# Altium.net
KiCad netlist of a schematic drawn in Altium Designer
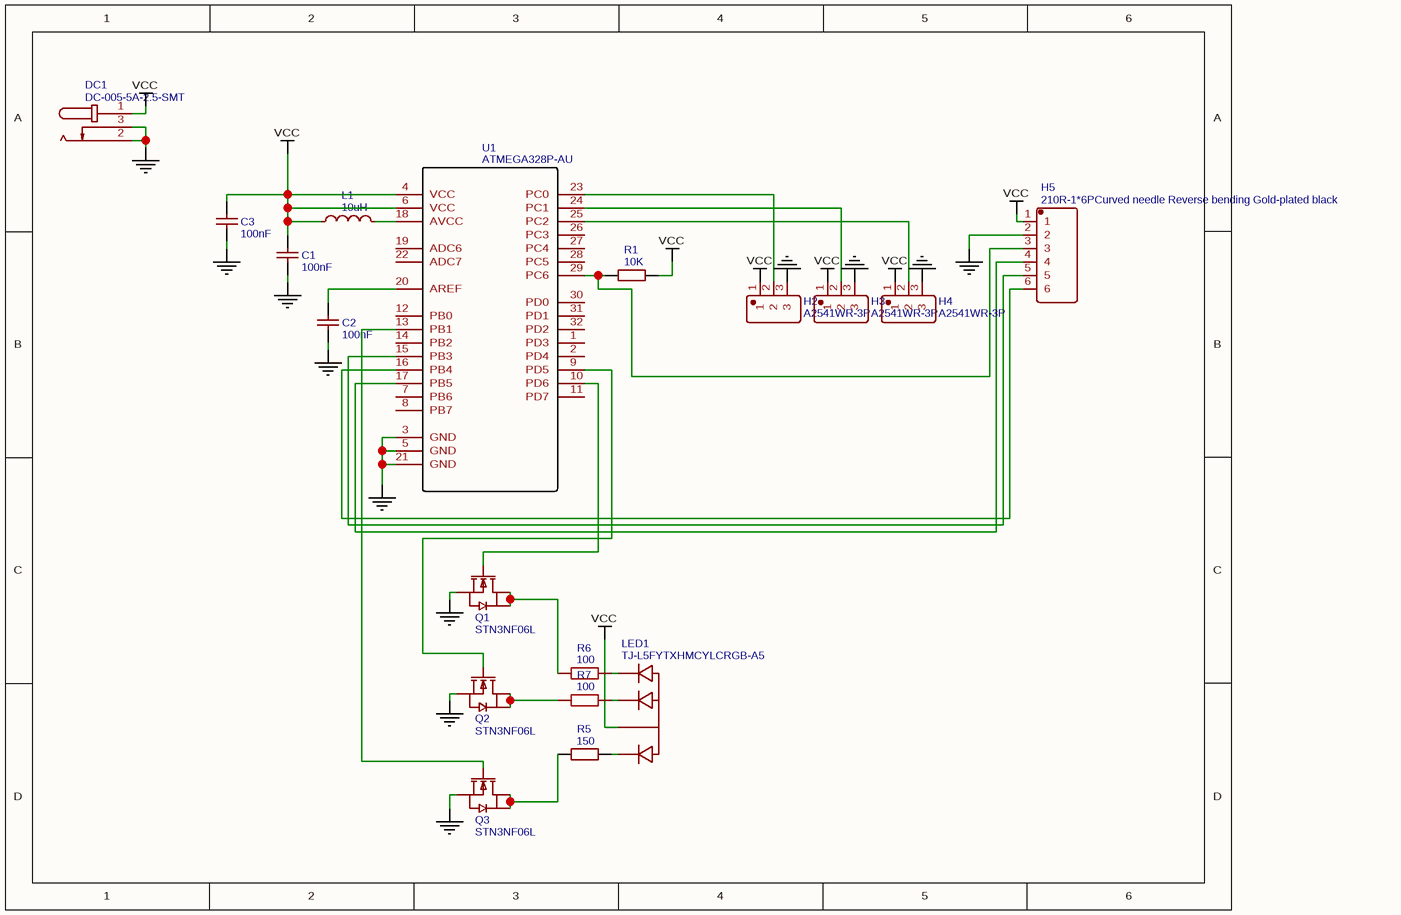
[diagram p0: Altium.schdoc]

(export (version "E")
  (design (tool "Eeschema 10.0.6"))
  (components
    (comp (ref "C1")
      (value "100nF")
      (fields
        (field (name "BOM_MANUFACTURER PART") "CC1206KKX7R0BB104")
        (field (name "BOM_SUPPLIER PART") "C107181")
      )
      (libsource (lib "altium-import") (part "root_1_100nF_"))
    )
    (comp (ref "C2")
      (value "100nF")
      (fields
        (field (name "BOM_MANUFACTURER PART") "CC1206KKX7R0BB104")
        (field (name "BOM_SUPPLIER PART") "C107181")
      )
      (libsource (lib "altium-import") (part "root_1_100nF_"))
    )
    (comp (ref "C3")
      (value "100nF")
      (fields
        (field (name "BOM_MANUFACTURER PART") "CC1206KKX7R0BB104")
        (field (name "BOM_SUPPLIER PART") "C107181")
      )
      (libsource (lib "altium-import") (part "root_1_100nF_"))
    )
    (comp (ref "DC1")
      (value "DC-005-5A-2.5-SMT")
      (fields (field (name "BOM_SUPPLIER PART") "C319133") (field (name "CONTRIBUTOR") "LCSC"))
      (libsource (lib "altium-import") (part "root_0_DC-005-5A-2.5-SMT_"))
    )
    (comp (ref "H2")
      (value "A2541WR-3P")
      (fields (field (name "BOM_SUPPLIER PART") "C225489") (field (name "CONTRIBUTOR") "LCSC"))
      (libsource (lib "altium-import") (part "root_2_A2541WR-3P_"))
    )
    (comp (ref "H3")
      (value "A2541WR-3P")
      (fields (field (name "BOM_SUPPLIER PART") "C225489") (field (name "CONTRIBUTOR") "LCSC"))
      (libsource (lib "altium-import") (part "root_2_A2541WR-3P_"))
    )
    (comp (ref "H4")
      (value "A2541WR-3P")
      (fields (field (name "BOM_SUPPLIER PART") "C225489") (field (name "CONTRIBUTOR") "LCSC"))
      (libsource (lib "altium-import") (part "root_2_A2541WR-3P_"))
    )
    (comp (ref "H5")
      (value "210R-1*6PCurved needle Reverse bending Gold-plated black")
      (fields (field (name "BOM_SUPPLIER PART") "C124367") (field (name "CONTRIBUTOR") "LCSC"))
      (libsource (lib "altium-import") (part "root_0_210R-1*6PCurved needle Reverse bending Gold-plated black_"))
    )
    (comp (ref "L1")
      (value "10uH")
      (fields
        (field (name "BOM_MANUFACTURER PART") "CMP321609XD100KT")
        (field (name "BOM_SUPPLIER PART") "C139251")
      )
      (libsource (lib "altium-import") (part "root_0_10uH_"))
    )
    (comp (ref "LED1")
      (value "TJ-L5FYTXHMCYLCRGB-A5")
      (fields (field (name "BOM_SUPPLIER PART") "C331057") (field (name "CONTRIBUTOR") "LCSC"))
      (libsource (lib "altium-import") (part "root_3_TJ-L5FYTXHMCYLCRGB-A5_"))
    )
    (comp (ref "Q1")
      (value "STN3NF06L")
      (fields (field (name "BOM_SUPPLIER PART") "C222218") (field (name "CONTRIBUTOR") "LCSC"))
      (libsource (lib "altium-import") (part "root_3_STN3NF06L_"))
    )
    (comp (ref "Q2")
      (value "STN3NF06L")
      (fields (field (name "BOM_SUPPLIER PART") "C222218") (field (name "CONTRIBUTOR") "LCSC"))
      (libsource (lib "altium-import") (part "root_3_STN3NF06L_"))
    )
    (comp (ref "Q3")
      (value "STN3NF06L")
      (fields (field (name "BOM_SUPPLIER PART") "C222218") (field (name "CONTRIBUTOR") "LCSC"))
      (libsource (lib "altium-import") (part "root_3_STN3NF06L_"))
    )
    (comp (ref "R1")
      (value "10K")
      (fields
        (field (name "BOM_MANUFACTURER PART") "1206W4F1002T5E")
        (field (name "BOM_SUPPLIER PART") "C17902")
      )
      (libsource (lib "altium-import") (part "root_0_10K_"))
    )
    (comp (ref "R5")
      (value "150")
      (fields
        (field (name "BOM_MANUFACTURER PART") "1206W4F1500T5E")
        (field (name "BOM_SUPPLIER PART") "C17917")
      )
      (libsource (lib "altium-import") (part "root_0_150_"))
    )
    (comp (ref "R6")
      (value "100")
      (fields
        (field (name "BOM_SUPPLIER PART") "C319959")
        (field (name "BOM_MANUFACTURER PART") "AR06DTCV1000")
        (field (name "CONTRIBUTOR") "LCSC")
      )
      (libsource (lib "altium-import") (part "root_0_100_"))
    )
    (comp (ref "R7")
      (value "100")
      (fields
        (field (name "BOM_SUPPLIER PART") "C319959")
        (field (name "BOM_MANUFACTURER PART") "AR06DTCV1000")
        (field (name "CONTRIBUTOR") "LCSC")
      )
      (libsource (lib "altium-import") (part "root_0_100_"))
    )
    (comp (ref "U1")
      (value "ATMEGA328P-AU")
      (fields (field (name "BOM_SUPPLIER PART") "C14877"))
      (libsource (lib "altium-import") (part "root_0_ATMEGA328P-AU_"))
    )
  )
  (nets
    (net (code "1") (name "GND") (class "Default")
      (node (ref "C1") (pin "1") (pinfunction "1_1") (pintype "passive"))
      (node (ref "C2") (pin "1") (pinfunction "1_1") (pintype "passive"))
      (node (ref "C3") (pin "1") (pinfunction "1_1") (pintype "passive"))
      (node (ref "DC1") (pin "2") (pinfunction "2_2") (pintype "passive"))
      (node (ref "DC1") (pin "3") (pinfunction "3_3") (pintype "passive"))
      (node (ref "H2") (pin "3") (pinfunction "3_3") (pintype "passive"))
      (node (ref "H3") (pin "3") (pinfunction "3_3") (pintype "passive"))
      (node (ref "H4") (pin "3") (pinfunction "3_3") (pintype "passive"))
      (node (ref "H5") (pin "2") (pinfunction "2_2") (pintype "passive"))
      (node (ref "Q1") (pin "3") (pinfunction "S_3") (pintype "passive"))
      (node (ref "Q2") (pin "3") (pinfunction "S_3") (pintype "passive"))
      (node (ref "Q3") (pin "3") (pinfunction "S_3") (pintype "passive"))
      (node (ref "U1") (pin "21") (pinfunction "GND_21") (pintype "passive"))
      (node (ref "U1") (pin "3") (pinfunction "GND_3") (pintype "passive"))
      (node (ref "U1") (pin "5") (pinfunction "GND_5") (pintype "passive"))
    )
    (net (code "2") (name "Net-(LED1-Pad1)") (class "Default")
      (node (ref "LED1") (pin "1") (pinfunction "1_1") (pintype "passive"))
      (node (ref "R5") (pin "2") (pinfunction "2_2") (pintype "passive"))
    )
    (net (code "3") (name "Net-(LED1-Pad3)") (class "Default")
      (node (ref "LED1") (pin "3") (pinfunction "3_3") (pintype "passive"))
      (node (ref "R7") (pin "2") (pinfunction "2_2") (pintype "passive"))
    )
    (net (code "4") (name "Net-(LED1-Pad4)") (class "Default")
      (node (ref "LED1") (pin "4") (pinfunction "4_4") (pintype "passive"))
      (node (ref "R6") (pin "2") (pinfunction "2_2") (pintype "passive"))
    )
    (net (code "5") (name "Net-(Q1-D-Pad2)") (class "Default")
      (node (ref "Q1") (pin "2") (pinfunction "D_2") (pintype "passive"))
      (node (ref "Q1") (pin "4") (pinfunction "D_4") (pintype "passive"))
      (node (ref "R6") (pin "1") (pinfunction "1_1") (pintype "passive"))
    )
    (net (code "6") (name "Net-(Q1-G)") (class "Default")
      (node (ref "Q1") (pin "1") (pinfunction "G_1") (pintype "passive"))
      (node (ref "U1") (pin "10") (pinfunction "PD6_10") (pintype "passive"))
    )
    (net (code "7") (name "Net-(Q2-D-Pad2)") (class "Default")
      (node (ref "Q2") (pin "2") (pinfunction "D_2") (pintype "passive"))
      (node (ref "Q2") (pin "4") (pinfunction "D_4") (pintype "passive"))
      (node (ref "R7") (pin "1") (pinfunction "1_1") (pintype "passive"))
    )
    (net (code "8") (name "Net-(Q2-G)") (class "Default")
      (node (ref "Q2") (pin "1") (pinfunction "G_1") (pintype "passive"))
      (node (ref "U1") (pin "9") (pinfunction "PD5_9") (pintype "passive"))
    )
    (net (code "9") (name "Net-(Q3-D-Pad2)") (class "Default")
      (node (ref "Q3") (pin "2") (pinfunction "D_2") (pintype "passive"))
      (node (ref "Q3") (pin "4") (pinfunction "D_4") (pintype "passive"))
      (node (ref "R5") (pin "1") (pinfunction "1_1") (pintype "passive"))
    )
    (net (code "10") (name "Net-(Q3-G)") (class "Default")
      (node (ref "Q3") (pin "1") (pinfunction "G_1") (pintype "passive"))
      (node (ref "U1") (pin "13") (pinfunction "PB1_13") (pintype "passive"))
    )
    (net (code "11") (name "Net-(U1-AREF)") (class "Default")
      (node (ref "C2") (pin "2") (pinfunction "2_2") (pintype "passive"))
      (node (ref "U1") (pin "20") (pinfunction "AREF_20") (pintype "passive"))
    )
    (net (code "12") (name "Net-(U1-AVCC)") (class "Default")
      (node (ref "L1") (pin "2") (pinfunction "2_2") (pintype "passive"))
      (node (ref "U1") (pin "18") (pinfunction "AVCC_18") (pintype "passive"))
    )
    (net (code "13") (name "Net-(U1-PB3)") (class "Default")
      (node (ref "H5") (pin "5") (pinfunction "5_5") (pintype "passive"))
      (node (ref "U1") (pin "15") (pinfunction "PB3_15") (pintype "passive"))
    )
    (net (code "14") (name "Net-(U1-PB4)") (class "Default")
      (node (ref "H5") (pin "6") (pinfunction "6_6") (pintype "passive"))
      (node (ref "U1") (pin "16") (pinfunction "PB4_16") (pintype "passive"))
    )
    (net (code "15") (name "Net-(U1-PB5)") (class "Default")
      (node (ref "H5") (pin "4") (pinfunction "4_4") (pintype "passive"))
      (node (ref "U1") (pin "17") (pinfunction "PB5_17") (pintype "passive"))
    )
    (net (code "16") (name "Net-(U1-PC0)") (class "Default")
      (node (ref "H2") (pin "2") (pinfunction "2_2") (pintype "passive"))
      (node (ref "U1") (pin "23") (pinfunction "PC0_23") (pintype "passive"))
    )
    (net (code "17") (name "Net-(U1-PC1)") (class "Default")
      (node (ref "H3") (pin "2") (pinfunction "2_2") (pintype "passive"))
      (node (ref "U1") (pin "24") (pinfunction "PC1_24") (pintype "passive"))
    )
    (net (code "18") (name "Net-(U1-PC2)") (class "Default")
      (node (ref "H4") (pin "2") (pinfunction "2_2") (pintype "passive"))
      (node (ref "U1") (pin "25") (pinfunction "PC2_25") (pintype "passive"))
    )
    (net (code "19") (name "Net-(U1-PC6)") (class "Default")
      (node (ref "H5") (pin "3") (pinfunction "3_3") (pintype "passive"))
      (node (ref "R1") (pin "1") (pinfunction "1_1") (pintype "passive"))
      (node (ref "U1") (pin "29") (pinfunction "PC6_29") (pintype "passive"))
    )
    (net (code "20") (name "VCC") (class "Default")
      (node (ref "C1") (pin "2") (pinfunction "2_2") (pintype "passive"))
      (node (ref "C3") (pin "2") (pinfunction "2_2") (pintype "passive"))
      (node (ref "DC1") (pin "1") (pinfunction "1_1") (pintype "passive"))
      (node (ref "H2") (pin "1") (pinfunction "1_1") (pintype "passive"))
      (node (ref "H3") (pin "1") (pinfunction "1_1") (pintype "passive"))
      (node (ref "H4") (pin "1") (pinfunction "1_1") (pintype "passive"))
      (node (ref "H5") (pin "1") (pinfunction "1_1") (pintype "passive"))
      (node (ref "L1") (pin "1") (pinfunction "1_1") (pintype "passive"))
      (node (ref "LED1") (pin "2") (pinfunction "+_2") (pintype "passive"))
      (node (ref "R1") (pin "2") (pinfunction "2_2") (pintype "passive"))
      (node (ref "U1") (pin "4") (pinfunction "VCC_4") (pintype "passive"))
      (node (ref "U1") (pin "6") (pinfunction "VCC_6") (pintype "passive"))
    )
    (net (code "21") (name "unconnected-(U1-ADC6-Pad19)") (class "Default")
      (node (ref "U1") (pin "19") (pinfunction "ADC6_19") (pintype "passive"))
    )
    (net (code "22") (name "unconnected-(U1-ADC7-Pad22)") (class "Default")
      (node (ref "U1") (pin "22") (pinfunction "ADC7_22") (pintype "passive"))
    )
    (net (code "23") (name "unconnected-(U1-PB0-Pad12)") (class "Default")
      (node (ref "U1") (pin "12") (pinfunction "PB0_12") (pintype "passive"))
    )
    (net (code "24") (name "unconnected-(U1-PB2-Pad14)") (class "Default")
      (node (ref "U1") (pin "14") (pinfunction "PB2_14") (pintype "passive"))
    )
    (net (code "25") (name "unconnected-(U1-PB6-Pad7)") (class "Default")
      (node (ref "U1") (pin "7") (pinfunction "PB6_7") (pintype "passive"))
    )
    (net (code "26") (name "unconnected-(U1-PB7-Pad8)") (class "Default")
      (node (ref "U1") (pin "8") (pinfunction "PB7_8") (pintype "passive"))
    )
    (net (code "27") (name "unconnected-(U1-PC3-Pad26)") (class "Default")
      (node (ref "U1") (pin "26") (pinfunction "PC3_26") (pintype "passive"))
    )
    (net (code "28") (name "unconnected-(U1-PC4-Pad27)") (class "Default")
      (node (ref "U1") (pin "27") (pinfunction "PC4_27") (pintype "passive"))
    )
    (net (code "29") (name "unconnected-(U1-PC5-Pad28)") (class "Default")
      (node (ref "U1") (pin "28") (pinfunction "PC5_28") (pintype "passive"))
    )
    (net (code "30") (name "unconnected-(U1-PD0-Pad30)") (class "Default")
      (node (ref "U1") (pin "30") (pinfunction "PD0_30") (pintype "passive"))
    )
    (net (code "31") (name "unconnected-(U1-PD1-Pad31)") (class "Default")
      (node (ref "U1") (pin "31") (pinfunction "PD1_31") (pintype "passive"))
    )
    (net (code "32") (name "unconnected-(U1-PD2-Pad32)") (class "Default")
      (node (ref "U1") (pin "32") (pinfunction "PD2_32") (pintype "passive"))
    )
    (net (code "33") (name "unconnected-(U1-PD3-Pad1)") (class "Default")
      (node (ref "U1") (pin "1") (pinfunction "PD3_1") (pintype "passive"))
    )
    (net (code "34") (name "unconnected-(U1-PD4-Pad2)") (class "Default")
      (node (ref "U1") (pin "2") (pinfunction "PD4_2") (pintype "passive"))
    )
    (net (code "35") (name "unconnected-(U1-PD7-Pad11)") (class "Default")
      (node (ref "U1") (pin "11") (pinfunction "PD7_11") (pintype "passive"))
    )
  )
)
